# WIFI_BLE_Option.net
KiCad netlist of a schematic drawn in Altium Designer
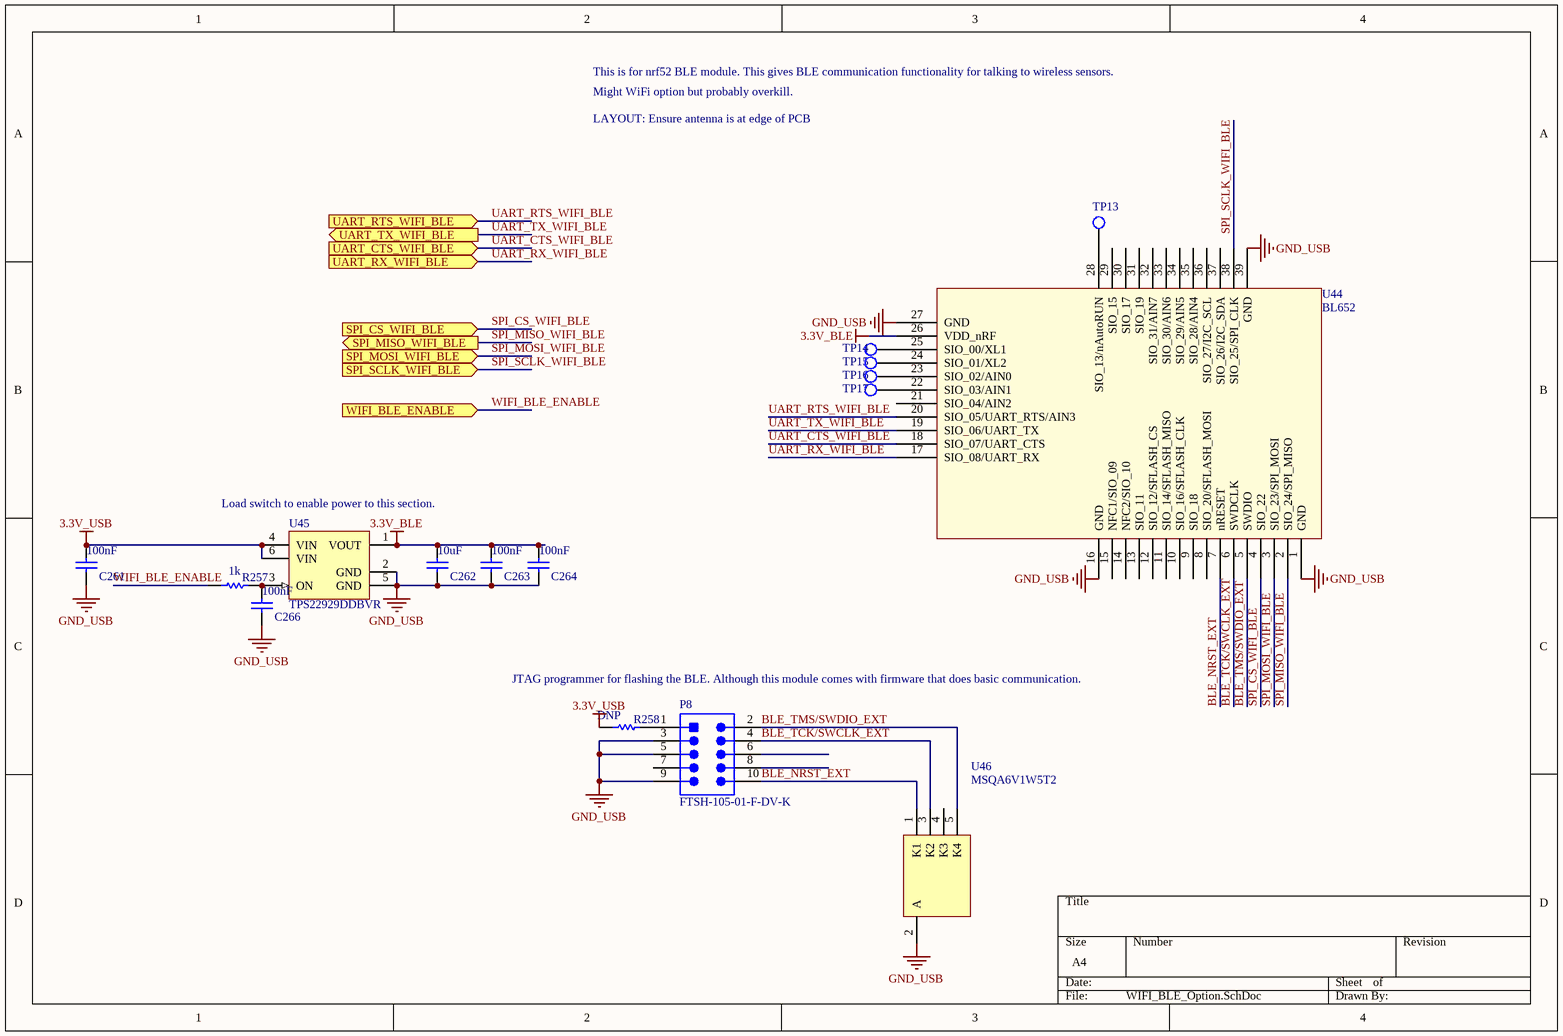
[diagram p0: WIFI_BLE_Option.SchDoc]

(export (version "E")
  (design (tool "Eeschema 10.0.6"))
  (components
    (comp (ref "C261")
      (value "100nF")
      (footprint "CAPC0402(1005)60_L")
      (description "0402 (1005 Metric) Chip Capacitor")
      (fields (field (name "Comment") "CAP0402"))
      (libsource (lib "Altium Content Vault") (part "CMP-1590-00004-1"))
    )
    (comp (ref "C262")
      (value "10uF")
      (footprint "CAPC0805(2012)145_L")
      (description "0805 (2012 Metric) Chip Capacitor")
      (fields (field (name "Comment") "CAP0805"))
      (libsource (lib "Altium Content Vault") (part "CMP-1590-00003-1"))
    )
    (comp (ref "C263")
      (value "100nF")
      (footprint "CAPC0402(1005)60_L")
      (description "0402 (1005 Metric) Chip Capacitor")
      (fields (field (name "Comment") "CAP0402"))
      (libsource (lib "Altium Content Vault") (part "CMP-1590-00004-1"))
    )
    (comp (ref "C264")
      (value "100nF")
      (footprint "CAPC0402(1005)60_L")
      (description "0402 (1005 Metric) Chip Capacitor")
      (fields (field (name "Comment") "CAP0402"))
      (libsource (lib "Altium Content Vault") (part "CMP-1590-00004-1"))
    )
    (comp (ref "C266")
      (value "100nF")
      (footprint "CAPC0402(1005)60_L")
      (description "0402 (1005 Metric) Chip Capacitor")
      (fields (field (name "Comment") "CAP0402"))
      (libsource (lib "Altium Content Vault") (part "CMP-1590-00004-1"))
    )
    (comp (ref "P8")
      (value "FTSH-105-01-F-DV-K")
      (footprint "SMTC-FTSH-105-01-L-DV-K_V")
      (description "Male Header, Pitch 1.27 mm, 2 x 5 Position, Height 6.12 mm, RoHS, Tube")
      (fields (field (name "MANUFACTURER") "Samtec"))
      (libsource (lib "Altium Content Vault") (part "CN-2P-M-R10"))
    )
    (comp (ref "R257")
      (value "1k")
      (footprint "RESC0402(1005)_L")
      (description "0402 (1005 Metric) Chip Resistor")
      (fields (field (name "Comment") "RES0402"))
      (libsource (lib "Altium Content Vault") (part "CMP-1591-00004-1"))
    )
    (comp (ref "R258")
      (value "DNP")
      (footprint "RESC0402(1005)_L")
      (description "0402 (1005 Metric) Chip Resistor")
      (fields (field (name "Comment") "RES0402"))
      (libsource (lib "Altium Content Vault") (part "CMP-1591-00004-1"))
    )
    (comp (ref "TP13")
      (value "Test Point")
      (footprint "Test_Point")
      (description "HARWIN  S1751-46R  PCB Test Point, S1751 Series, Surface Mount, Copper Alloy, Tin Plated Contacts")
      (fields (field (name "MANUFACTURER") "HARWIN") (field (name "MANUFACTURER PART NUMBER") "S1751-46R"))
      (libsource (lib "Kilian_UCC_Library") (part "Test_Point"))
    )
    (comp (ref "TP14")
      (value "Test Point")
      (footprint "Test_Point")
      (description "HARWIN  S1751-46R  PCB Test Point, S1751 Series, Surface Mount, Copper Alloy, Tin Plated Contacts")
      (fields (field (name "MANUFACTURER") "HARWIN") (field (name "MANUFACTURER PART NUMBER") "S1751-46R"))
      (libsource (lib "Kilian_UCC_Library") (part "Test_Point"))
    )
    (comp (ref "TP15")
      (value "Test Point")
      (footprint "Test_Point")
      (description "HARWIN  S1751-46R  PCB Test Point, S1751 Series, Surface Mount, Copper Alloy, Tin Plated Contacts")
      (fields (field (name "MANUFACTURER") "HARWIN") (field (name "MANUFACTURER PART NUMBER") "S1751-46R"))
      (libsource (lib "Kilian_UCC_Library") (part "Test_Point"))
    )
    (comp (ref "TP16")
      (value "Test Point")
      (footprint "Test_Point")
      (description "HARWIN  S1751-46R  PCB Test Point, S1751 Series, Surface Mount, Copper Alloy, Tin Plated Contacts")
      (fields (field (name "MANUFACTURER") "HARWIN") (field (name "MANUFACTURER PART NUMBER") "S1751-46R"))
      (libsource (lib "Kilian_UCC_Library") (part "Test_Point"))
    )
    (comp (ref "TP17")
      (value "Test Point")
      (footprint "Test_Point")
      (description "HARWIN  S1751-46R  PCB Test Point, S1751 Series, Surface Mount, Copper Alloy, Tin Plated Contacts")
      (fields (field (name "MANUFACTURER") "HARWIN") (field (name "MANUFACTURER PART NUMBER") "S1751-46R"))
      (libsource (lib "Kilian_UCC_Library") (part "Test_Point"))
    )
    (comp (ref "U44")
      (value "BL652")
      (footprint "BL652")
      (fields
        (field (name "MANUFACTURER") "Laird - Wireless & Thermal Systems")
        (field (name "MANUFACTURER PART NUMBER") "BL652-SA-01-T/R")
        (field (name "UTILIZED IC / PART") "nRF52832")
      )
      (libsource (lib "DAQ_Replacement") (part "BL652"))
    )
    (comp (ref "U45")
      (value "TPS22929DDBVR")
      (footprint "DBV6_N")
      (fields (field (name "MANUFACTURER") "Texas Instruments"))
      (libsource (lib "Altium Content Vault") (part "TI-TPS22929DDBV6"))
    )
    (comp (ref "U46")
      (value "MSQA6V1W5T2")
      (footprint "ONSC-SC70-5-419A-02_V")
      (description "Quad Array ESD Protection Diodes with Low Clamping Voltage, 5-Pin SC70, Tape and Reel")
      (fields (field (name "MANUFACTURER") "On Semiconductor"))
      (libsource (lib "Altium Content Vault") (part "ONSC-MSQA6V1W5-SC70-5-419A-02"))
    )
  )
  (nets
    (net (code "1") (name "/BLE_NRST_EXT") (class "Default")
      (node (ref "P8") (pin "10") (pinfunction "10_10") (pintype "passive"))
      (node (ref "U44") (pin "7") (pinfunction "nRESET_7") (pintype "passive"))
      (node (ref "U46") (pin "1") (pinfunction "K1_1") (pintype "passive"))
    )
    (net (code "2") (name "/BLE_TCK{slash}SWCLK_EXT") (class "Default")
      (node (ref "P8") (pin "4") (pinfunction "4_4") (pintype "passive"))
      (node (ref "U44") (pin "6") (pinfunction "SWDCLK_6") (pintype "passive"))
      (node (ref "U46") (pin "3") (pinfunction "K2_3") (pintype "passive"))
    )
    (net (code "3") (name "/BLE_TMS{slash}SWDIO_EXT") (class "Default")
      (node (ref "P8") (pin "2") (pinfunction "2_2") (pintype "passive"))
      (node (ref "U44") (pin "5") (pinfunction "SWDIO_5") (pintype "passive"))
      (node (ref "U46") (pin "5") (pinfunction "K4_5") (pintype "passive"))
    )
    (net (code "4") (name "/SPI_CS_WIFI_BLE") (class "Default")
      (node (ref "U44") (pin "4") (pinfunction "SIO_22_4") (pintype "passive"))
    )
    (net (code "5") (name "/SPI_MISO_WIFI_BLE") (class "Default")
      (node (ref "U44") (pin "2") (pinfunction "SIO_24/SPI_MISO_2") (pintype "passive"))
    )
    (net (code "6") (name "/SPI_MOSI_WIFI_BLE") (class "Default")
      (node (ref "U44") (pin "3") (pinfunction "SIO_23/SPI_MOSI_3") (pintype "passive"))
    )
    (net (code "7") (name "/SPI_SCLK_WIFI_BLE") (class "Default")
      (node (ref "U44") (pin "38") (pinfunction "SIO_25/SPI_CLK_38") (pintype "passive"))
    )
    (net (code "8") (name "/UART_CTS_WIFI_BLE") (class "Default")
      (node (ref "U44") (pin "18") (pinfunction "SIO_07/UART_CTS_18") (pintype "passive"))
    )
    (net (code "9") (name "/UART_RTS_WIFI_BLE") (class "Default")
      (node (ref "U44") (pin "20") (pinfunction "SIO_05/UART_RTS/AIN3_20") (pintype "passive"))
    )
    (net (code "10") (name "/UART_RX_WIFI_BLE") (class "Default")
      (node (ref "U44") (pin "17") (pinfunction "SIO_08/UART_RX_17") (pintype "passive"))
    )
    (net (code "11") (name "/UART_TX_WIFI_BLE") (class "Default")
      (node (ref "U44") (pin "19") (pinfunction "SIO_06/UART_TX_19") (pintype "passive"))
    )
    (net (code "12") (name "/WIFI_BLE_ENABLE") (class "Default")
      (node (ref "R257") (pin "2") (pinfunction "2_2") (pintype "passive"))
    )
    (net (code "13") (name "3.3V_BLE") (class "Default")
      (node (ref "C262") (pin "2") (pinfunction "2_2") (pintype "passive"))
      (node (ref "C263") (pin "1") (pinfunction "1_1") (pintype "passive"))
      (node (ref "C264") (pin "1") (pinfunction "1_1") (pintype "passive"))
      (node (ref "U44") (pin "26") (pinfunction "VDD_nRF_26") (pintype "passive"))
      (node (ref "U45") (pin "1") (pinfunction "VOUT_1") (pintype "power_in"))
    )
    (net (code "14") (name "3.3V_USB") (class "Default")
      (node (ref "C261") (pin "1") (pinfunction "1_1") (pintype "passive"))
      (node (ref "R258") (pin "2") (pinfunction "2_2") (pintype "passive"))
      (node (ref "U45") (pin "4") (pinfunction "VIN_4") (pintype "power_in"))
      (node (ref "U45") (pin "6") (pinfunction "VIN_6") (pintype "power_in"))
    )
    (net (code "15") (name "GND_USB") (class "Default")
      (node (ref "C261") (pin "2") (pinfunction "2_2") (pintype "passive"))
      (node (ref "C262") (pin "1") (pinfunction "1_1") (pintype "passive"))
      (node (ref "C263") (pin "2") (pinfunction "2_2") (pintype "passive"))
      (node (ref "C264") (pin "2") (pinfunction "2_2") (pintype "passive"))
      (node (ref "C266") (pin "2") (pinfunction "2_2") (pintype "passive"))
      (node (ref "P8") (pin "3") (pinfunction "3_3") (pintype "passive"))
      (node (ref "P8") (pin "5") (pinfunction "5_5") (pintype "passive"))
      (node (ref "P8") (pin "9") (pinfunction "9_9") (pintype "passive"))
      (node (ref "U44") (pin "1") (pinfunction "GND_1") (pintype "passive"))
      (node (ref "U44") (pin "16") (pinfunction "GND_16") (pintype "passive"))
      (node (ref "U44") (pin "27") (pinfunction "GND_27") (pintype "passive"))
      (node (ref "U44") (pin "39") (pinfunction "GND_39") (pintype "passive"))
      (node (ref "U45") (pin "2") (pinfunction "GND_2") (pintype "power_in"))
      (node (ref "U45") (pin "5") (pinfunction "GND_5") (pintype "power_in"))
      (node (ref "U46") (pin "2") (pinfunction "A_2") (pintype "passive"))
    )
    (net (code "16") (name "Net-(P8-Pad1)") (class "Default")
      (node (ref "P8") (pin "1") (pinfunction "1_1") (pintype "passive"))
      (node (ref "R258") (pin "1") (pinfunction "1_1") (pintype "passive"))
    )
    (net (code "17") (name "Net-(TP13-TP)") (class "Default")
      (node (ref "TP13") (pin "1") (pinfunction "TP_1") (pintype "passive"))
      (node (ref "U44") (pin "28") (pinfunction "SIO_13/nAutoRUN_28") (pintype "passive"))
    )
    (net (code "18") (name "Net-(TP14-TP)") (class "Default")
      (node (ref "TP14") (pin "1") (pinfunction "TP_1") (pintype "passive"))
      (node (ref "U44") (pin "25") (pinfunction "SIO_00/XL1_25") (pintype "passive"))
    )
    (net (code "19") (name "Net-(TP15-TP)") (class "Default")
      (node (ref "TP15") (pin "1") (pinfunction "TP_1") (pintype "passive"))
      (node (ref "U44") (pin "24") (pinfunction "SIO_01/XL2_24") (pintype "passive"))
    )
    (net (code "20") (name "Net-(TP16-TP)") (class "Default")
      (node (ref "TP16") (pin "1") (pinfunction "TP_1") (pintype "passive"))
      (node (ref "U44") (pin "23") (pinfunction "SIO_02/AIN0_23") (pintype "passive"))
    )
    (net (code "21") (name "Net-(TP17-TP)") (class "Default")
      (node (ref "TP17") (pin "1") (pinfunction "TP_1") (pintype "passive"))
      (node (ref "U44") (pin "22") (pinfunction "SIO_03/AIN1_22") (pintype "passive"))
    )
    (net (code "22") (name "Net-(U45-ON)") (class "Default")
      (node (ref "C266") (pin "1") (pinfunction "1_1") (pintype "passive"))
      (node (ref "R257") (pin "1") (pinfunction "1_1") (pintype "passive"))
      (node (ref "U45") (pin "3") (pinfunction "ON_3") (pintype "input"))
    )
    (net (code "23") (name "unconnected-(P8-Pad6)") (class "Default")
      (node (ref "P8") (pin "6") (pinfunction "6_6") (pintype "passive"))
    )
    (net (code "24") (name "unconnected-(P8-Pad7)") (class "Default")
      (node (ref "P8") (pin "7") (pinfunction "7_7") (pintype "passive"))
    )
    (net (code "25") (name "unconnected-(P8-Pad8)") (class "Default")
      (node (ref "P8") (pin "8") (pinfunction "8_8") (pintype "passive"))
    )
    (net (code "26") (name "unconnected-(U44-NFC1{slash}SIO_09-Pad15)") (class "Default")
      (node (ref "U44") (pin "15") (pinfunction "NFC1/SIO_09_15") (pintype "passive"))
    )
    (net (code "27") (name "unconnected-(U44-NFC2{slash}SIO_10-Pad14)") (class "Default")
      (node (ref "U44") (pin "14") (pinfunction "NFC2/SIO_10_14") (pintype "passive"))
    )
    (net (code "28") (name "unconnected-(U44-SIO_04{slash}AIN2-Pad21)") (class "Default")
      (node (ref "U44") (pin "21") (pinfunction "SIO_04/AIN2_21") (pintype "passive"))
    )
    (net (code "29") (name "unconnected-(U44-SIO_11-Pad13)") (class "Default")
      (node (ref "U44") (pin "13") (pinfunction "SIO_11_13") (pintype "passive"))
    )
    (net (code "30") (name "unconnected-(U44-SIO_12{slash}SFLASH_CS-Pad12)") (class "Default")
      (node (ref "U44") (pin "12") (pinfunction "SIO_12/SFLASH_CS_12") (pintype "passive"))
    )
    (net (code "31") (name "unconnected-(U44-SIO_14{slash}SFLASH_MISO-Pad11)") (class "Default")
      (node (ref "U44") (pin "11") (pinfunction "SIO_14/SFLASH_MISO_11") (pintype "passive"))
    )
    (net (code "32") (name "unconnected-(U44-SIO_15-Pad29)") (class "Default")
      (node (ref "U44") (pin "29") (pinfunction "SIO_15_29") (pintype "passive"))
    )
    (net (code "33") (name "unconnected-(U44-SIO_16{slash}SFLASH_CLK-Pad10)") (class "Default")
      (node (ref "U44") (pin "10") (pinfunction "SIO_16/SFLASH_CLK_10") (pintype "passive"))
    )
    (net (code "34") (name "unconnected-(U44-SIO_17-Pad30)") (class "Default")
      (node (ref "U44") (pin "30") (pinfunction "SIO_17_30") (pintype "passive"))
    )
    (net (code "35") (name "unconnected-(U44-SIO_18-Pad9)") (class "Default")
      (node (ref "U44") (pin "9") (pinfunction "SIO_18_9") (pintype "passive"))
    )
    (net (code "36") (name "unconnected-(U44-SIO_19-Pad31)") (class "Default")
      (node (ref "U44") (pin "31") (pinfunction "SIO_19_31") (pintype "passive"))
    )
    (net (code "37") (name "unconnected-(U44-SIO_20{slash}SFLASH_MOSI-Pad8)") (class "Default")
      (node (ref "U44") (pin "8") (pinfunction "SIO_20/SFLASH_MOSI_8") (pintype "passive"))
    )
    (net (code "38") (name "unconnected-(U44-SIO_26{slash}I2C_SDA-Pad37)") (class "Default")
      (node (ref "U44") (pin "37") (pinfunction "SIO_26/I2C_SDA_37") (pintype "passive"))
    )
    (net (code "39") (name "unconnected-(U44-SIO_27{slash}I2C_SCL-Pad36)") (class "Default")
      (node (ref "U44") (pin "36") (pinfunction "SIO_27/I2C_SCL_36") (pintype "passive"))
    )
    (net (code "40") (name "unconnected-(U44-SIO_28{slash}AIN4-Pad35)") (class "Default")
      (node (ref "U44") (pin "35") (pinfunction "SIO_28/AIN4_35") (pintype "passive"))
    )
    (net (code "41") (name "unconnected-(U44-SIO_29{slash}AIN5-Pad34)") (class "Default")
      (node (ref "U44") (pin "34") (pinfunction "SIO_29/AIN5_34") (pintype "passive"))
    )
    (net (code "42") (name "unconnected-(U44-SIO_30{slash}AIN6-Pad33)") (class "Default")
      (node (ref "U44") (pin "33") (pinfunction "SIO_30/AIN6_33") (pintype "passive"))
    )
    (net (code "43") (name "unconnected-(U44-SIO_31{slash}AIN7-Pad32)") (class "Default")
      (node (ref "U44") (pin "32") (pinfunction "SIO_31/AIN7_32") (pintype "passive"))
    )
    (net (code "44") (name "unconnected-(U46-K3-Pad4)") (class "Default")
      (node (ref "U46") (pin "4") (pinfunction "K3_4") (pintype "passive"))
    )
  )
)
